# BALANCER.net
KiCad netlist of a schematic drawn in Altium Designer
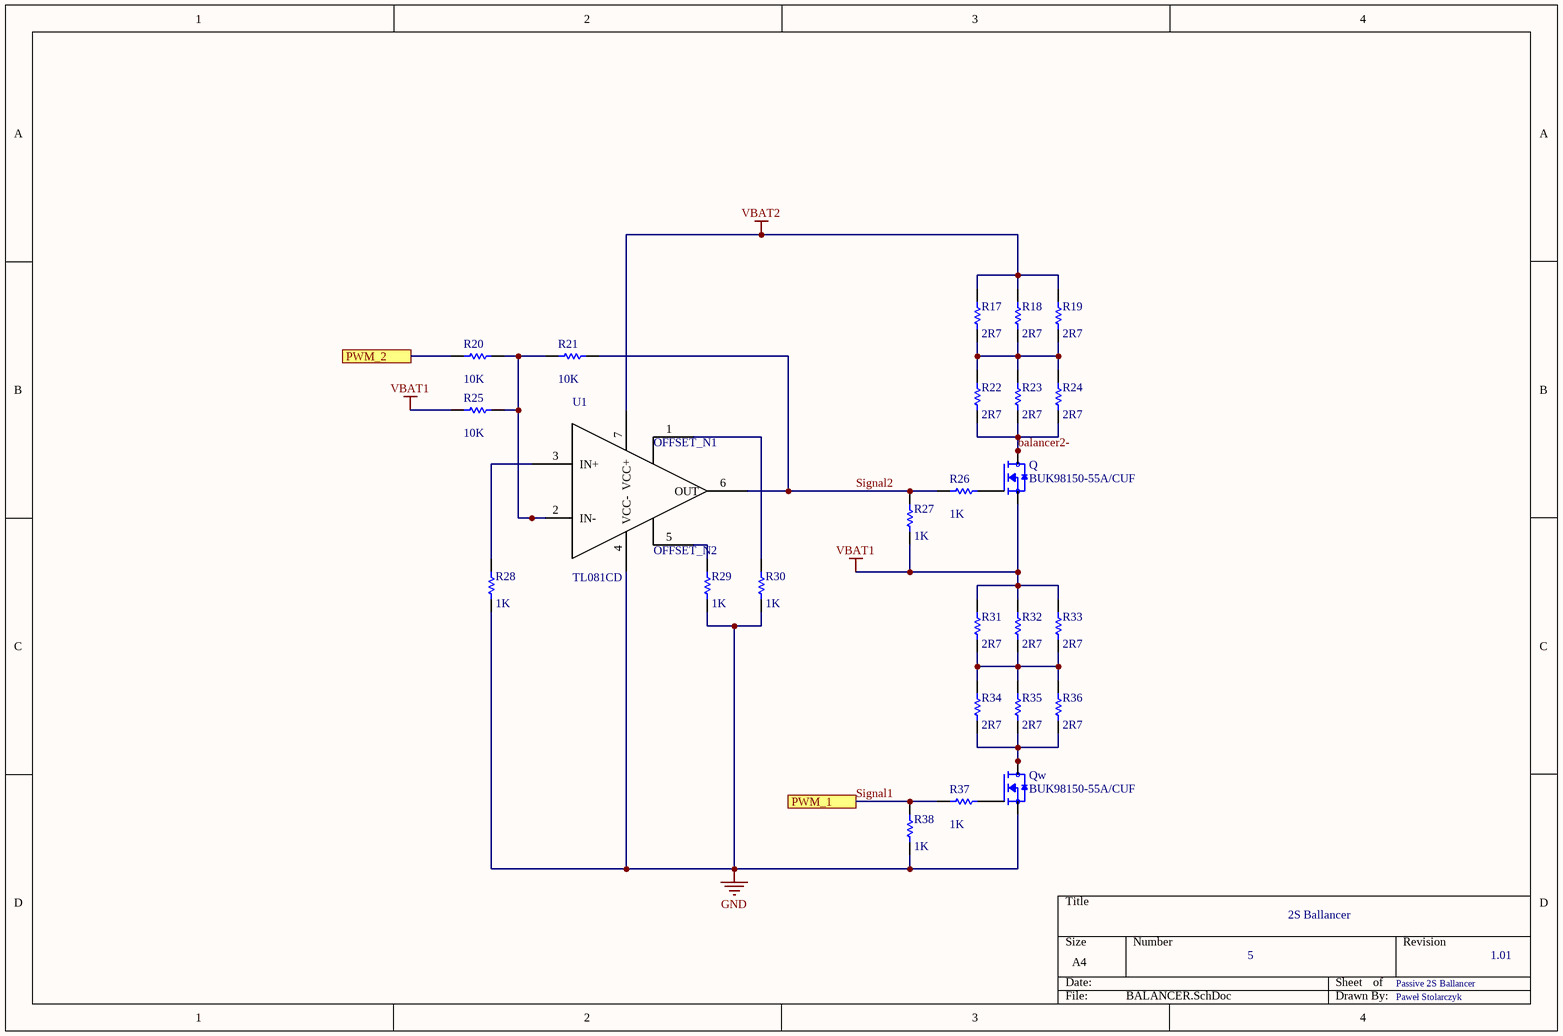
[diagram p0: BALANCER.SchDoc]

(export (version "E")
  (design (tool "Eeschema 10.0.6"))
  (components
    (comp (ref "Q")
      (value "BUK98150-55A/CUF")
      (footprint "SOT230P700X180-4N")
      (description "N-Channel 55V 5.5A _Tc_ 8W _Tc_ Surface Mount SOT-223")
      (fields (field (name "MF") "Nexperia USA"))
      (libsource (lib "BUK98150-55A_CUF") (part "BUK98150-55A/CUF"))
    )
    (comp (ref "Qw")
      (value "BUK98150-55A/CUF")
      (footprint "SOT230P700X180-4N")
      (description "N-Channel 55V 5.5A _Tc_ 8W _Tc_ Surface Mount SOT-223")
      (fields (field (name "MF") "Nexperia USA"))
      (libsource (lib "BUK98150-55A_CUF") (part "BUK98150-55A/CUF"))
    )
    (comp (ref "R17")
      (value "2R7")
      (footprint "C2512")
      (description "Resistor")
      (fields (field (name "Comment") "Res1") (field (name "PUBLISHER") "Altium Limited"))
      (libsource (lib "Miscellaneous Devices") (part "Res1"))
    )
    (comp (ref "R18")
      (value "2R7")
      (footprint "C2512")
      (description "Resistor")
      (fields (field (name "Comment") "Res1") (field (name "PUBLISHER") "Altium Limited"))
      (libsource (lib "Miscellaneous Devices") (part "Res1"))
    )
    (comp (ref "R19")
      (value "2R7")
      (footprint "C2512")
      (description "Resistor")
      (fields (field (name "Comment") "Res1") (field (name "PUBLISHER") "Altium Limited"))
      (libsource (lib "Miscellaneous Devices") (part "Res1"))
    )
    (comp (ref "R20")
      (value "10K")
      (footprint "0402")
      (description "Resistor")
      (fields (field (name "Comment") "Res1") (field (name "PUBLISHER") "Altium Limited"))
      (libsource (lib "Miscellaneous Devices") (part "Res1"))
    )
    (comp (ref "R21")
      (value "10K")
      (footprint "0402")
      (description "Resistor")
      (fields (field (name "Comment") "Res1") (field (name "PUBLISHER") "Altium Limited"))
      (libsource (lib "Miscellaneous Devices") (part "Res1"))
    )
    (comp (ref "R22")
      (value "2R7")
      (footprint "C2512")
      (description "Resistor")
      (fields (field (name "Comment") "Res1") (field (name "PUBLISHER") "Altium Limited"))
      (libsource (lib "Miscellaneous Devices") (part "Res1"))
    )
    (comp (ref "R23")
      (value "2R7")
      (footprint "C2512")
      (description "Resistor")
      (fields (field (name "Comment") "Res1") (field (name "PUBLISHER") "Altium Limited"))
      (libsource (lib "Miscellaneous Devices") (part "Res1"))
    )
    (comp (ref "R24")
      (value "2R7")
      (footprint "C2512")
      (description "Resistor")
      (fields (field (name "Comment") "Res1") (field (name "PUBLISHER") "Altium Limited"))
      (libsource (lib "Miscellaneous Devices") (part "Res1"))
    )
    (comp (ref "R25")
      (value "10K")
      (footprint "0402")
      (description "Resistor")
      (fields (field (name "Comment") "Res1") (field (name "PUBLISHER") "Altium Limited"))
      (libsource (lib "Miscellaneous Devices") (part "Res1"))
    )
    (comp (ref "R26")
      (value "1K")
      (footprint "0402")
      (description "Resistor")
      (fields (field (name "Comment") "Res1") (field (name "PUBLISHER") "Altium Limited"))
      (libsource (lib "Miscellaneous Devices") (part "Res1"))
    )
    (comp (ref "R27")
      (value "1K")
      (footprint "0402")
      (description "Resistor")
      (fields (field (name "Comment") "Res1") (field (name "PUBLISHER") "Altium Limited"))
      (libsource (lib "Miscellaneous Devices") (part "Res1"))
    )
    (comp (ref "R28")
      (value "1K")
      (footprint "0402")
      (description "Resistor")
      (fields (field (name "Comment") "Res1") (field (name "PUBLISHER") "Altium Limited"))
      (libsource (lib "Miscellaneous Devices") (part "Res1"))
    )
    (comp (ref "R29")
      (value "1K")
      (footprint "0402")
      (description "Resistor")
      (fields (field (name "Comment") "Res1") (field (name "PUBLISHER") "Altium Limited"))
      (libsource (lib "Miscellaneous Devices") (part "Res1"))
    )
    (comp (ref "R30")
      (value "1K")
      (footprint "0402")
      (description "Resistor")
      (fields (field (name "Comment") "Res1") (field (name "PUBLISHER") "Altium Limited"))
      (libsource (lib "Miscellaneous Devices") (part "Res1"))
    )
    (comp (ref "R31")
      (value "2R7")
      (footprint "C2512")
      (description "Resistor")
      (fields (field (name "Comment") "Res1") (field (name "PUBLISHER") "Altium Limited"))
      (libsource (lib "Miscellaneous Devices") (part "Res1"))
    )
    (comp (ref "R32")
      (value "2R7")
      (footprint "C2512")
      (description "Resistor")
      (fields (field (name "Comment") "Res1") (field (name "PUBLISHER") "Altium Limited"))
      (libsource (lib "Miscellaneous Devices") (part "Res1"))
    )
    (comp (ref "R33")
      (value "2R7")
      (footprint "C2512")
      (description "Resistor")
      (fields (field (name "Comment") "Res1") (field (name "PUBLISHER") "Altium Limited"))
      (libsource (lib "Miscellaneous Devices") (part "Res1"))
    )
    (comp (ref "R34")
      (value "2R7")
      (footprint "C2512")
      (description "Resistor")
      (fields (field (name "Comment") "Res1") (field (name "PUBLISHER") "Altium Limited"))
      (libsource (lib "Miscellaneous Devices") (part "Res1"))
    )
    (comp (ref "R35")
      (value "2R7")
      (footprint "C2512")
      (description "Resistor")
      (fields (field (name "Comment") "Res1") (field (name "PUBLISHER") "Altium Limited"))
      (libsource (lib "Miscellaneous Devices") (part "Res1"))
    )
    (comp (ref "R36")
      (value "2R7")
      (footprint "C2512")
      (description "Resistor")
      (fields (field (name "Comment") "Res1") (field (name "PUBLISHER") "Altium Limited"))
      (libsource (lib "Miscellaneous Devices") (part "Res1"))
    )
    (comp (ref "R37")
      (value "1K")
      (footprint "0402")
      (description "Resistor")
      (fields (field (name "Comment") "Res1") (field (name "PUBLISHER") "Altium Limited"))
      (libsource (lib "Miscellaneous Devices") (part "Res1"))
    )
    (comp (ref "R38")
      (value "1K")
      (footprint "0402")
      (description "Resistor")
      (fields (field (name "Comment") "Res1") (field (name "PUBLISHER") "Altium Limited"))
      (libsource (lib "Miscellaneous Devices") (part "Res1"))
    )
    (comp (ref "U1")
      (value "TL081CD")
      (footprint "SOIC127P599X175-8N")
      (description "High Slew Rate JFET-Input Operational Amplifier 8-SOIC 0 to 70")
      (fields (field (name "MF") "Texas Instruments"))
      (libsource (lib "ten_TL081CD") (part "TL081CD"))
    )
  )
  (nets
    (net (code "1") (name "/PWM_2") (class "Default")
      (node (ref "R20") (pin "1") (pinfunction "1_1") (pintype "passive"))
    )
    (net (code "2") (name "/Signal1") (class "Default")
      (node (ref "R37") (pin "1") (pinfunction "1_1") (pintype "passive"))
      (node (ref "R38") (pin "2") (pinfunction "2_2") (pintype "passive"))
    )
    (net (code "3") (name "/Signal2") (class "Default")
      (node (ref "R21") (pin "2") (pinfunction "2_2") (pintype "passive"))
      (node (ref "R26") (pin "1") (pinfunction "1_1") (pintype "passive"))
      (node (ref "R27") (pin "2") (pinfunction "2_2") (pintype "passive"))
      (node (ref "U1") (pin "6") (pinfunction "OUT_6") (pintype "passive"))
    )
    (net (code "4") (name "/balancer2-") (class "Default")
      (node (ref "Q") (pin "2") (pinfunction "D_2") (pintype "passive"))
      (node (ref "Q") (pin "4") (pinfunction "D_4") (pintype "passive"))
      (node (ref "R22") (pin "1") (pinfunction "1_1") (pintype "passive"))
      (node (ref "R23") (pin "1") (pinfunction "1_1") (pintype "passive"))
      (node (ref "R24") (pin "1") (pinfunction "1_1") (pintype "passive"))
    )
    (net (code "5") (name "GND") (class "Default")
      (node (ref "Qw") (pin "3") (pinfunction "S_3") (pintype "passive"))
      (node (ref "R28") (pin "1") (pinfunction "1_1") (pintype "passive"))
      (node (ref "R29") (pin "1") (pinfunction "1_1") (pintype "passive"))
      (node (ref "R30") (pin "1") (pinfunction "1_1") (pintype "passive"))
      (node (ref "R38") (pin "1") (pinfunction "1_1") (pintype "passive"))
      (node (ref "U1") (pin "4") (pinfunction "VCC-_4") (pintype "passive"))
    )
    (net (code "6") (name "Net-(Q-G)") (class "Default")
      (node (ref "Q") (pin "1") (pinfunction "G_1") (pintype "passive"))
      (node (ref "R26") (pin "2") (pinfunction "2_2") (pintype "passive"))
    )
    (net (code "7") (name "Net-(Qw-D-Pad2)") (class "Default")
      (node (ref "Qw") (pin "2") (pinfunction "D_2") (pintype "passive"))
      (node (ref "Qw") (pin "4") (pinfunction "D_4") (pintype "passive"))
      (node (ref "R34") (pin "1") (pinfunction "1_1") (pintype "passive"))
      (node (ref "R35") (pin "1") (pinfunction "1_1") (pintype "passive"))
      (node (ref "R36") (pin "1") (pinfunction "1_1") (pintype "passive"))
    )
    (net (code "8") (name "Net-(Qw-G)") (class "Default")
      (node (ref "Qw") (pin "1") (pinfunction "G_1") (pintype "passive"))
      (node (ref "R37") (pin "2") (pinfunction "2_2") (pintype "passive"))
    )
    (net (code "9") (name "Net-(R17-Pad1)") (class "Default")
      (node (ref "R17") (pin "1") (pinfunction "1_1") (pintype "passive"))
      (node (ref "R18") (pin "1") (pinfunction "1_1") (pintype "passive"))
      (node (ref "R19") (pin "1") (pinfunction "1_1") (pintype "passive"))
      (node (ref "R22") (pin "2") (pinfunction "2_2") (pintype "passive"))
      (node (ref "R23") (pin "2") (pinfunction "2_2") (pintype "passive"))
      (node (ref "R24") (pin "2") (pinfunction "2_2") (pintype "passive"))
    )
    (net (code "10") (name "Net-(R31-Pad1)") (class "Default")
      (node (ref "R31") (pin "1") (pinfunction "1_1") (pintype "passive"))
      (node (ref "R32") (pin "1") (pinfunction "1_1") (pintype "passive"))
      (node (ref "R33") (pin "1") (pinfunction "1_1") (pintype "passive"))
      (node (ref "R34") (pin "2") (pinfunction "2_2") (pintype "passive"))
      (node (ref "R35") (pin "2") (pinfunction "2_2") (pintype "passive"))
      (node (ref "R36") (pin "2") (pinfunction "2_2") (pintype "passive"))
    )
    (net (code "11") (name "Net-(U1-IN+)") (class "Default")
      (node (ref "R28") (pin "2") (pinfunction "2_2") (pintype "passive"))
      (node (ref "U1") (pin "3") (pinfunction "IN+_3") (pintype "passive"))
    )
    (net (code "12") (name "Net-(U1-IN-)") (class "Default")
      (node (ref "R20") (pin "2") (pinfunction "2_2") (pintype "passive"))
      (node (ref "R21") (pin "1") (pinfunction "1_1") (pintype "passive"))
      (node (ref "R25") (pin "2") (pinfunction "2_2") (pintype "passive"))
      (node (ref "U1") (pin "2") (pinfunction "IN-_2") (pintype "passive"))
    )
    (net (code "13") (name "Net-(U1-OFFSET_N1)") (class "Default")
      (node (ref "R30") (pin "2") (pinfunction "2_2") (pintype "passive"))
      (node (ref "U1") (pin "1") (pinfunction "OFFSET_N1_1") (pintype "passive"))
    )
    (net (code "14") (name "Net-(U1-OFFSET_N2)") (class "Default")
      (node (ref "R29") (pin "2") (pinfunction "2_2") (pintype "passive"))
      (node (ref "U1") (pin "5") (pinfunction "OFFSET_N2_5") (pintype "passive"))
    )
    (net (code "15") (name "VBAT1") (class "Default")
      (node (ref "Q") (pin "3") (pinfunction "S_3") (pintype "passive"))
      (node (ref "R25") (pin "1") (pinfunction "1_1") (pintype "passive"))
      (node (ref "R27") (pin "1") (pinfunction "1_1") (pintype "passive"))
      (node (ref "R31") (pin "2") (pinfunction "2_2") (pintype "passive"))
      (node (ref "R32") (pin "2") (pinfunction "2_2") (pintype "passive"))
      (node (ref "R33") (pin "2") (pinfunction "2_2") (pintype "passive"))
    )
    (net (code "16") (name "VBAT2") (class "Default")
      (node (ref "R17") (pin "2") (pinfunction "2_2") (pintype "passive"))
      (node (ref "R18") (pin "2") (pinfunction "2_2") (pintype "passive"))
      (node (ref "R19") (pin "2") (pinfunction "2_2") (pintype "passive"))
      (node (ref "U1") (pin "7") (pinfunction "VCC+_7") (pintype "passive"))
    )
  )
)
